# hsArduino.net
KiCad netlist of a schematic drawn in EAGLE
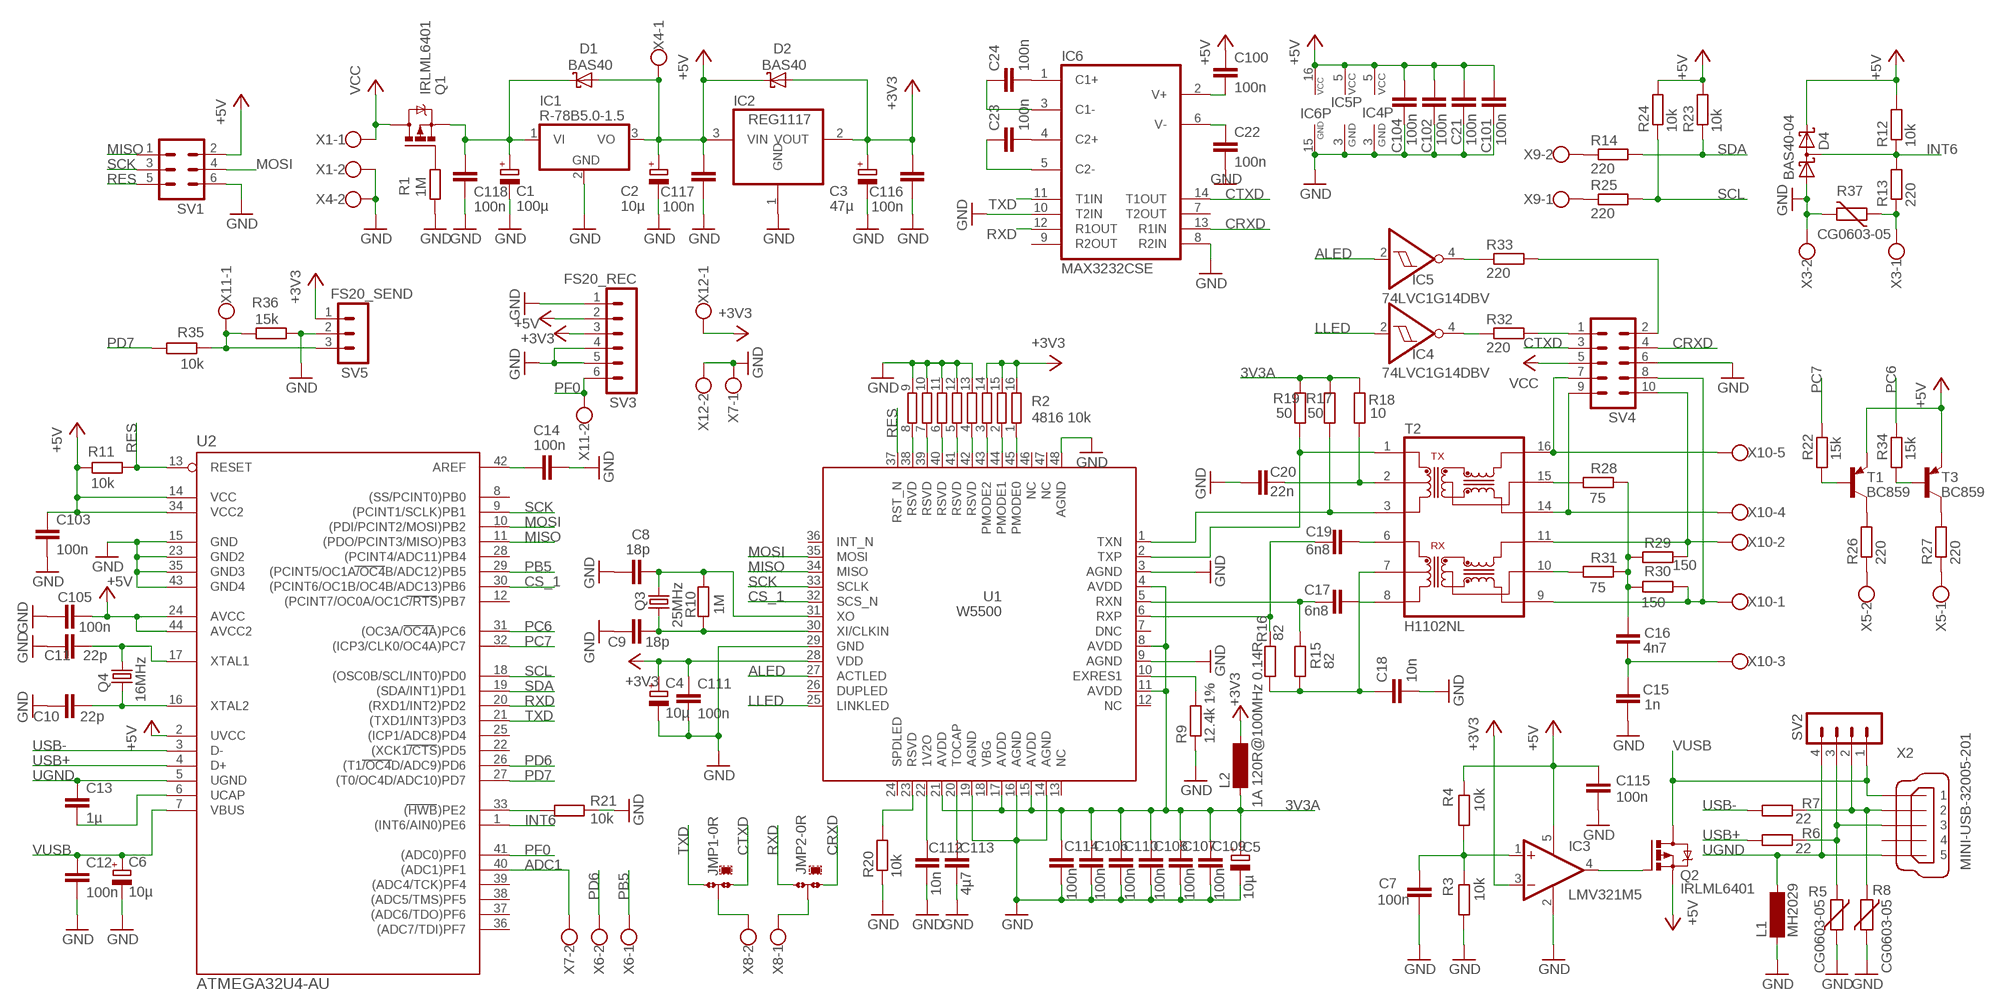
[diagram p0: schematic, sheet 1]

(export (version "E")
  (design (tool "Eeschema 10.0.6"))
  (components
    (comp (ref "C1")
      (value "100µ")
      (footprint "eagle-import:E2,5-7")
      (libsource (lib "eagle-import") (part "CPOL-EUE2.5-7"))
    )
    (comp (ref "C2")
      (value "10µ")
      (footprint "eagle-import:E2-5")
      (libsource (lib "eagle-import") (part "CPOL-EUE2-5"))
    )
    (comp (ref "C3")
      (value "47µ")
      (footprint "eagle-import:E2-5")
      (libsource (lib "eagle-import") (part "CPOL-EUE2-5"))
    )
    (comp (ref "C4")
      (value "10µ")
      (footprint "eagle-import:E2-5")
      (libsource (lib "eagle-import") (part "CPOL-EUE2-5"))
    )
    (comp (ref "C5")
      (value "10µ")
      (footprint "eagle-import:E2-5")
      (libsource (lib "eagle-import") (part "CPOL-EUE2-5"))
    )
    (comp (ref "C6")
      (value "10µ")
      (footprint "eagle-import:E2-5")
      (libsource (lib "eagle-import") (part "CPOL-EUE2-5"))
    )
    (comp (ref "C7")
      (value "100n")
      (footprint "eagle-import:C0805K")
      (libsource (lib "eagle-import") (part "C-EUC0805K"))
    )
    (comp (ref "C8")
      (value "18p")
      (footprint "eagle-import:C0805K")
      (libsource (lib "eagle-import") (part "C-EUC0805K"))
    )
    (comp (ref "C9")
      (value "18p")
      (footprint "eagle-import:C0805K")
      (libsource (lib "eagle-import") (part "C-EUC0805K"))
    )
    (comp (ref "C10")
      (value "22p")
      (footprint "eagle-import:C0805K")
      (libsource (lib "eagle-import") (part "C-EUC0805K"))
    )
    (comp (ref "C11")
      (value "22p")
      (footprint "eagle-import:C0805K")
      (libsource (lib "eagle-import") (part "C-EUC0805K"))
    )
    (comp (ref "C12")
      (value "100n")
      (footprint "eagle-import:C0805K")
      (libsource (lib "eagle-import") (part "C-EUC0805K"))
    )
    (comp (ref "C13")
      (value "1µ")
      (footprint "eagle-import:C0805K")
      (libsource (lib "eagle-import") (part "C-EUC0805K"))
    )
    (comp (ref "C14")
      (value "100n")
      (footprint "eagle-import:C0805K")
      (libsource (lib "eagle-import") (part "C-EUC0805K"))
    )
    (comp (ref "C15")
      (value "1n")
      (footprint "eagle-import:C0805K")
      (libsource (lib "eagle-import") (part "C-EUC0805K"))
    )
    (comp (ref "C16")
      (value "4n7")
      (footprint "eagle-import:C0805K")
      (libsource (lib "eagle-import") (part "C-EUC0805K"))
    )
    (comp (ref "C17")
      (value "6n8")
      (footprint "eagle-import:C0805K")
      (libsource (lib "eagle-import") (part "C-EUC0805K"))
    )
    (comp (ref "C18")
      (value "10n")
      (footprint "eagle-import:C0805K")
      (libsource (lib "eagle-import") (part "C-EUC0805K"))
    )
    (comp (ref "C19")
      (value "6n8")
      (footprint "eagle-import:C0805K")
      (libsource (lib "eagle-import") (part "C-EUC0805K"))
    )
    (comp (ref "C20")
      (value "22n")
      (footprint "eagle-import:C0805K")
      (libsource (lib "eagle-import") (part "C-EUC0805K"))
    )
    (comp (ref "C21")
      (value "100n")
      (footprint "eagle-import:C0805K")
      (libsource (lib "eagle-import") (part "C-EUC0805K"))
    )
    (comp (ref "C22")
      (value "100n")
      (footprint "eagle-import:C0805K")
      (libsource (lib "eagle-import") (part "C-EUC0805K"))
    )
    (comp (ref "C23")
      (value "100n")
      (footprint "eagle-import:C0805K")
      (libsource (lib "eagle-import") (part "C-EUC0805K"))
    )
    (comp (ref "C24")
      (value "100n")
      (footprint "eagle-import:C0805K")
      (libsource (lib "eagle-import") (part "C-EUC0805K"))
    )
    (comp (ref "C100")
      (value "100n")
      (footprint "eagle-import:C0805K")
      (libsource (lib "eagle-import") (part "C-EUC0805K"))
    )
    (comp (ref "C101")
      (value "100n")
      (footprint "eagle-import:C0805K")
      (libsource (lib "eagle-import") (part "C-EUC0805K"))
    )
    (comp (ref "C102")
      (value "100n")
      (footprint "eagle-import:C0805K")
      (libsource (lib "eagle-import") (part "C-EUC0805K"))
    )
    (comp (ref "C103")
      (value "100n")
      (footprint "eagle-import:C0805K")
      (libsource (lib "eagle-import") (part "C-EUC0805K"))
    )
    (comp (ref "C104")
      (value "100n")
      (footprint "eagle-import:C0805K")
      (libsource (lib "eagle-import") (part "C-EUC0805K"))
    )
    (comp (ref "C105")
      (value "100n")
      (footprint "eagle-import:C0805K")
      (libsource (lib "eagle-import") (part "C-EUC0805K"))
    )
    (comp (ref "C106")
      (value "100n")
      (footprint "eagle-import:C0805K")
      (libsource (lib "eagle-import") (part "C-EUC0805K"))
    )
    (comp (ref "C107")
      (value "100n")
      (footprint "eagle-import:C0805K")
      (libsource (lib "eagle-import") (part "C-EUC0805K"))
    )
    (comp (ref "C108")
      (value "100n")
      (footprint "eagle-import:C0805K")
      (libsource (lib "eagle-import") (part "C-EUC0805K"))
    )
    (comp (ref "C109")
      (value "100n")
      (footprint "eagle-import:C0805K")
      (libsource (lib "eagle-import") (part "C-EUC0805K"))
    )
    (comp (ref "C110")
      (value "100n")
      (footprint "eagle-import:C0805K")
      (libsource (lib "eagle-import") (part "C-EUC0805K"))
    )
    (comp (ref "C111")
      (value "100n")
      (footprint "eagle-import:C0805K")
      (libsource (lib "eagle-import") (part "C-EUC0805K"))
    )
    (comp (ref "C112")
      (value "10n")
      (footprint "eagle-import:C0805K")
      (libsource (lib "eagle-import") (part "C-EUC0805K"))
    )
    (comp (ref "C113")
      (value "4µ7")
      (footprint "eagle-import:C0805K")
      (libsource (lib "eagle-import") (part "C-EUC0805K"))
    )
    (comp (ref "C114")
      (value "100n")
      (footprint "eagle-import:C0805K")
      (libsource (lib "eagle-import") (part "C-EUC0805K"))
    )
    (comp (ref "C115")
      (value "100n")
      (footprint "eagle-import:C0805K")
      (libsource (lib "eagle-import") (part "C-EUC0805K"))
    )
    (comp (ref "C116")
      (value "100n")
      (footprint "eagle-import:C0805K")
      (libsource (lib "eagle-import") (part "C-EUC0805K"))
    )
    (comp (ref "C117")
      (value "100n")
      (footprint "eagle-import:C0805K")
      (libsource (lib "eagle-import") (part "C-EUC0805K"))
    )
    (comp (ref "C118")
      (value "100n")
      (footprint "eagle-import:C0805K")
      (libsource (lib "eagle-import") (part "C-EUC0805K"))
    )
    (comp (ref "D1")
      (value "BAS40")
      (footprint "eagle-import:SOT23")
      (libsource (lib "eagle-import") (part "BAS40"))
    )
    (comp (ref "D2")
      (value "BAS40")
      (footprint "eagle-import:SOT23")
      (libsource (lib "eagle-import") (part "BAS40"))
    )
    (comp (ref "D4")
      (value "BAS40-04")
      (footprint "eagle-import:SOT23")
      (libsource (lib "eagle-import") (part "BAS40-04"))
    )
    (comp (ref "IC1")
      (value "R-78B5.0-1.5")
      (footprint "eagle-import:TO220V")
      (libsource (lib "eagle-import") (part "78TV05"))
    )
    (comp (ref "IC2")
      (value "REG1117")
      (footprint "eagle-import:SOT223")
      (libsource (lib "eagle-import") (part "REG1117"))
    )
    (comp (ref "IC3")
      (value "LMV321M5")
      (footprint "eagle-import:SOT23-5")
      (libsource (lib "eagle-import") (part "LMV321?M5"))
    )
    (comp (ref "IC4")
      (value "74LVC1G14DBV")
      (footprint "eagle-import:SOT23-5")
      (libsource (lib "eagle-import") (part "741G14DBVLVC"))
    )
    (comp (ref "IC5")
      (value "74LVC1G14DBV")
      (footprint "eagle-import:SOT23-5")
      (libsource (lib "eagle-import") (part "741G14DBVLVC"))
    )
    (comp (ref "IC6")
      (value "MAX3232CSE")
      (footprint "eagle-import:SO16")
      (libsource (lib "eagle-import") (part "MAX3232SEC"))
    )
    (comp (ref "JMP1")
      (value "0R-JUMPA")
      (footprint "eagle-import:A0R-JMP")
      (libsource (lib "eagle-import") (part "0R-JUMPA"))
    )
    (comp (ref "JMP2")
      (value "0R-JUMPA")
      (footprint "eagle-import:A0R-JMP")
      (libsource (lib "eagle-import") (part "0R-JUMPA"))
    )
    (comp (ref "L1")
      (value "MH2029")
      (footprint "eagle-import:SM-1206")
      (libsource (lib "eagle-import") (part "SM-1206"))
    )
    (comp (ref "L2")
      (value "1A 120R@100MHz 0.14R")
      (footprint "eagle-import:SM-1206")
      (libsource (lib "eagle-import") (part "SM-1206"))
    )
    (comp (ref "Q1")
      (value "IRLML6401")
      (footprint "eagle-import:MICRO3")
      (libsource (lib "eagle-import") (part "IRLML5203"))
    )
    (comp (ref "Q2")
      (value "IRLML6401")
      (footprint "eagle-import:MICRO3")
      (libsource (lib "eagle-import") (part "IRLML5203"))
    )
    (comp (ref "Q3")
      (value "25MHz")
      (footprint "eagle-import:HC49_S")
      (libsource (lib "eagle-import") (part "CRYSTALHC49S"))
    )
    (comp (ref "Q4")
      (value "16MHz")
      (footprint "eagle-import:HC49_S")
      (libsource (lib "eagle-import") (part "CRYSTALHC49S"))
    )
    (comp (ref "R1")
      (value "1M")
      (footprint "eagle-import:R0805")
      (libsource (lib "eagle-import") (part "R-EU_R0805"))
    )
    (comp (ref "R2")
      (value "4816 10k")
      (footprint "eagle-import:4816P")
      (fields (field (name "MF") "BOURNS, INC.") (field (name "MPN") "4816P-T01-684LF"))
      (libsource (lib "eagle-import") (part "4816P-T01"))
    )
    (comp (ref "R3")
      (value "10k")
      (footprint "eagle-import:R0805")
      (libsource (lib "eagle-import") (part "R-EU_R0805"))
    )
    (comp (ref "R4")
      (value "10k")
      (footprint "eagle-import:R0805")
      (libsource (lib "eagle-import") (part "R-EU_R0805"))
    )
    (comp (ref "R5")
      (value "CG0603-05")
      (footprint "eagle-import:CT_CN0603")
      (libsource (lib "eagle-import") (part "VARISTORCN0603"))
    )
    (comp (ref "R6")
      (value "22")
      (footprint "eagle-import:R0805")
      (libsource (lib "eagle-import") (part "R-EU_R0805"))
    )
    (comp (ref "R7")
      (value "22")
      (footprint "eagle-import:R0805")
      (libsource (lib "eagle-import") (part "R-EU_R0805"))
    )
    (comp (ref "R8")
      (value "CG0603-05")
      (footprint "eagle-import:CT_CN0603")
      (libsource (lib "eagle-import") (part "VARISTORCN0603"))
    )
    (comp (ref "R9")
      (value "12.4k 1%")
      (footprint "eagle-import:R0805")
      (libsource (lib "eagle-import") (part "R-EU_R0805"))
    )
    (comp (ref "R10")
      (value "1M")
      (footprint "eagle-import:R0805")
      (libsource (lib "eagle-import") (part "R-EU_R0805"))
    )
    (comp (ref "R11")
      (value "10k")
      (footprint "eagle-import:R0805")
      (libsource (lib "eagle-import") (part "R-EU_R0805"))
    )
    (comp (ref "R12")
      (value "10k")
      (footprint "eagle-import:R0805")
      (libsource (lib "eagle-import") (part "R-EU_R0805"))
    )
    (comp (ref "R13")
      (value "220")
      (footprint "eagle-import:R0805")
      (libsource (lib "eagle-import") (part "R-EU_R0805"))
    )
    (comp (ref "R14")
      (value "220")
      (footprint "eagle-import:R0805")
      (libsource (lib "eagle-import") (part "R-EU_R0805"))
    )
    (comp (ref "R15")
      (value "82")
      (footprint "eagle-import:R0805")
      (libsource (lib "eagle-import") (part "R-EU_R0805"))
    )
    (comp (ref "R16")
      (value "82")
      (footprint "eagle-import:R0805")
      (libsource (lib "eagle-import") (part "R-EU_R0805"))
    )
    (comp (ref "R17")
      (value "50")
      (footprint "eagle-import:R0805")
      (libsource (lib "eagle-import") (part "R-EU_R0805"))
    )
    (comp (ref "R18")
      (value "10")
      (footprint "eagle-import:R0805")
      (libsource (lib "eagle-import") (part "R-EU_R0805"))
    )
    (comp (ref "R19")
      (value "50")
      (footprint "eagle-import:R0805")
      (libsource (lib "eagle-import") (part "R-EU_R0805"))
    )
    (comp (ref "R20")
      (value "10k")
      (footprint "eagle-import:R0805")
      (libsource (lib "eagle-import") (part "R-EU_R0805"))
    )
    (comp (ref "R21")
      (value "10k")
      (footprint "eagle-import:R0805")
      (libsource (lib "eagle-import") (part "R-EU_R0805"))
    )
    (comp (ref "R22")
      (value "15k")
      (footprint "eagle-import:R0805")
      (libsource (lib "eagle-import") (part "R-EU_R0805"))
    )
    (comp (ref "R23")
      (value "10k")
      (footprint "eagle-import:R0805")
      (libsource (lib "eagle-import") (part "R-EU_R0805"))
    )
    (comp (ref "R24")
      (value "10k")
      (footprint "eagle-import:R0805")
      (libsource (lib "eagle-import") (part "R-EU_R0805"))
    )
    (comp (ref "R25")
      (value "220")
      (footprint "eagle-import:R0805")
      (libsource (lib "eagle-import") (part "R-EU_R0805"))
    )
    (comp (ref "R26")
      (value "220")
      (footprint "eagle-import:R0805")
      (libsource (lib "eagle-import") (part "R-EU_R0805"))
    )
    (comp (ref "R27")
      (value "220")
      (footprint "eagle-import:R0805")
      (libsource (lib "eagle-import") (part "R-EU_R0805"))
    )
    (comp (ref "R28")
      (value "75")
      (footprint "eagle-import:R0805")
      (libsource (lib "eagle-import") (part "R-EU_R0805"))
    )
    (comp (ref "R29")
      (value "150")
      (footprint "eagle-import:R0805")
      (libsource (lib "eagle-import") (part "R-EU_R0805"))
    )
    (comp (ref "R30")
      (value "150")
      (footprint "eagle-import:R0805")
      (libsource (lib "eagle-import") (part "R-EU_R0805"))
    )
    (comp (ref "R31")
      (value "75")
      (footprint "eagle-import:R0805")
      (libsource (lib "eagle-import") (part "R-EU_R0805"))
    )
    (comp (ref "R32")
      (value "220")
      (footprint "eagle-import:R0805")
      (libsource (lib "eagle-import") (part "R-EU_R0805"))
    )
    (comp (ref "R33")
      (value "220")
      (footprint "eagle-import:R0805")
      (libsource (lib "eagle-import") (part "R-EU_R0805"))
    )
    (comp (ref "R34")
      (value "15k")
      (footprint "eagle-import:R0805")
      (libsource (lib "eagle-import") (part "R-EU_R0805"))
    )
    (comp (ref "R35")
      (value "10k")
      (footprint "eagle-import:R0805")
      (libsource (lib "eagle-import") (part "R-EU_R0805"))
    )
    (comp (ref "R36")
      (value "15k")
      (footprint "eagle-import:R0805")
      (libsource (lib "eagle-import") (part "R-EU_R0805"))
    )
    (comp (ref "R37")
      (value "CG0603-05")
      (footprint "eagle-import:CT_CN0603")
      (libsource (lib "eagle-import") (part "VARISTORCN0603"))
    )
    (comp (ref "SV1")
      (value "ML6")
      (footprint "eagle-import:ML6")
      (libsource (lib "eagle-import") (part "ML6"))
    )
    (comp (ref "SV2")
      (value "MA04-1")
      (footprint "eagle-import:MA04-1")
      (libsource (lib "eagle-import") (part "MA04-1"))
    )
    (comp (ref "SV3")
      (value "FS20_REC")
      (footprint "eagle-import:MA06-1")
      (libsource (lib "eagle-import") (part "MA06-1"))
    )
    (comp (ref "SV4")
      (value "ML10")
      (footprint "eagle-import:ML10")
      (libsource (lib "eagle-import") (part "ML10"))
    )
    (comp (ref "SV5")
      (value "FS20_SEND")
      (footprint "eagle-import:MA03-1")
      (libsource (lib "eagle-import") (part "MA03-1"))
    )
    (comp (ref "T1")
      (value "BC859")
      (footprint "eagle-import:SOT23-BEC")
      (libsource (lib "eagle-import") (part "-PNP-SOT23-BECBC857A"))
    )
    (comp (ref "T2")
      (value "H1102NL")
      (footprint "eagle-import:HXXXX")
      (libsource (lib "eagle-import") (part "HX1188"))
    )
    (comp (ref "T3")
      (value "BC859")
      (footprint "eagle-import:SOT23-BEC")
      (libsource (lib "eagle-import") (part "-PNP-SOT23-BECBC857A"))
    )
    (comp (ref "U1")
      (value "W5500")
      (footprint "eagle-import:W5500")
      (libsource (lib "eagle-import") (part "W5500"))
    )
    (comp (ref "U2")
      (value "ATMEGA32U4-AU")
      (footprint "eagle-import:TQFP44")
      (libsource (lib "eagle-import") (part "ATMEGA32U4-AU"))
    )
    (comp (ref "X1")
      (value "W237-02P")
      (footprint "eagle-import:W237-132")
      (libsource (lib "eagle-import") (part "W237-02P"))
    )
    (comp (ref "X2")
      (value "MINI-USB-32005-201")
      (footprint "eagle-import:32005-201")
      (libsource (lib "eagle-import") (part "MINI-USB-32005-201"))
    )
    (comp (ref "X3")
      (value "W237-02P")
      (footprint "eagle-import:W237-132")
      (libsource (lib "eagle-import") (part "W237-02P"))
    )
    (comp (ref "X4")
      (value "W237-02P")
      (footprint "eagle-import:W237-132")
      (libsource (lib "eagle-import") (part "W237-02P"))
    )
    (comp (ref "X5")
      (value "W237-02P")
      (footprint "eagle-import:W237-132")
      (libsource (lib "eagle-import") (part "W237-02P"))
    )
    (comp (ref "X6")
      (value "W237-02P")
      (footprint "eagle-import:W237-132")
      (libsource (lib "eagle-import") (part "W237-02P"))
    )
    (comp (ref "X7")
      (value "W237-02P")
      (footprint "eagle-import:W237-132")
      (libsource (lib "eagle-import") (part "W237-02P"))
    )
    (comp (ref "X8")
      (value "W237-02P")
      (footprint "eagle-import:W237-132")
      (libsource (lib "eagle-import") (part "W237-02P"))
    )
    (comp (ref "X9")
      (value "W237-02P")
      (footprint "eagle-import:W237-132")
      (libsource (lib "eagle-import") (part "W237-02P"))
    )
    (comp (ref "X10")
      (value "W237-05P")
      (footprint "eagle-import:W237-5P")
      (libsource (lib "eagle-import") (part "W237-05P"))
    )
    (comp (ref "X11")
      (value "W237-02P")
      (footprint "eagle-import:W237-132")
      (libsource (lib "eagle-import") (part "W237-02P"))
    )
    (comp (ref "X12")
      (value "W237-02P")
      (footprint "eagle-import:W237-132")
      (libsource (lib "eagle-import") (part "W237-02P"))
    )
  )
  (nets
    (net (code "1") (name "+3V3") (class "Default")
      (node (ref "C111") (pin "1") (pinfunction "1_1") (pintype "passive"))
      (node (ref "C116") (pin "2") (pinfunction "2_2") (pintype "passive"))
      (node (ref "C3") (pin "+") (pinfunction "+_+") (pintype "passive"))
      (node (ref "C4") (pin "+") (pinfunction "+_+") (pintype "passive"))
      (node (ref "D2") (pin "1") (pinfunction "A_1") (pintype "passive"))
      (node (ref "IC2") (pin "2") (pinfunction "VOUT_2") (pintype "output"))
      (node (ref "IC3") (pin "3") (pinfunction "-IN_3") (pintype "input"))
      (node (ref "L2") (pin "2") (pinfunction "2_2") (pintype "passive"))
      (node (ref "R2") (pin "14") (pinfunction "14_14") (pintype "passive"))
      (node (ref "R2") (pin "15") (pinfunction "15_15") (pintype "passive"))
      (node (ref "R2") (pin "16") (pinfunction "16_16") (pintype "passive"))
      (node (ref "SV3") (pin "3") (pinfunction "3_3") (pintype "passive"))
      (node (ref "SV5") (pin "1") (pinfunction "1_1") (pintype "passive"))
      (node (ref "U1") (pin "28") (pinfunction "VDD_28") (pintype "passive"))
      (node (ref "X12") (pin "1") (pinfunction "KL_1") (pintype "passive"))
    )
    (net (code "2") (name "+5V") (class "Default")
      (node (ref "C100") (pin "1") (pinfunction "1_1") (pintype "passive"))
      (node (ref "C101") (pin "1") (pinfunction "1_1") (pintype "passive"))
      (node (ref "C102") (pin "2") (pinfunction "2_2") (pintype "passive"))
      (node (ref "C103") (pin "1") (pinfunction "1_1") (pintype "passive"))
      (node (ref "C104") (pin "2") (pinfunction "2_2") (pintype "passive"))
      (node (ref "C105") (pin "1") (pinfunction "1_1") (pintype "passive"))
      (node (ref "C115") (pin "2") (pinfunction "2_2") (pintype "passive"))
      (node (ref "C117") (pin "2") (pinfunction "2_2") (pintype "passive"))
      (node (ref "C2") (pin "+") (pinfunction "+_+") (pintype "passive"))
      (node (ref "C21") (pin "1") (pinfunction "1_1") (pintype "passive"))
      (node (ref "D1") (pin "1") (pinfunction "A_1") (pintype "passive"))
      (node (ref "D2") (pin "3") (pinfunction "C_3") (pintype "passive"))
      (node (ref "D4") (pin "2") (pinfunction "C2_2") (pintype "passive"))
      (node (ref "IC1") (pin "3") (pinfunction "VO_3") (pintype "passive"))
      (node (ref "IC2") (pin "3") (pinfunction "VIN_3") (pintype "input"))
      (node (ref "IC3") (pin "5") (pinfunction "V+_5") (pintype "power_in"))
      (node (ref "IC4") (pin "5") (pinfunction "VCC_5") (pintype "power_in"))
      (node (ref "IC5") (pin "5") (pinfunction "VCC_5") (pintype "power_in"))
      (node (ref "IC6") (pin "16") (pinfunction "VCC_16") (pintype "power_in"))
      (node (ref "Q2") (pin "2") (pinfunction "S_2") (pintype "passive"))
      (node (ref "R11") (pin "2") (pinfunction "2_2") (pintype "passive"))
      (node (ref "R12") (pin "2") (pinfunction "2_2") (pintype "passive"))
      (node (ref "R23") (pin "2") (pinfunction "2_2") (pintype "passive"))
      (node (ref "R24") (pin "2") (pinfunction "2_2") (pintype "passive"))
      (node (ref "R4") (pin "1") (pinfunction "1_1") (pintype "passive"))
      (node (ref "SV1") (pin "2") (pinfunction "2_2") (pintype "passive"))
      (node (ref "SV3") (pin "2") (pinfunction "2_2") (pintype "passive"))
      (node (ref "T1") (pin "E") (pinfunction "E_E") (pintype "passive"))
      (node (ref "T3") (pin "E") (pinfunction "E_E") (pintype "passive"))
      (node (ref "U2") (pin "14") (pinfunction "VCC_14") (pintype "bidirectional"))
      (node (ref "U2") (pin "2") (pinfunction "UVCC_2") (pintype "bidirectional"))
      (node (ref "U2") (pin "24") (pinfunction "AVCC_24") (pintype "bidirectional"))
      (node (ref "U2") (pin "34") (pinfunction "VCC2_34") (pintype "bidirectional"))
      (node (ref "U2") (pin "44") (pinfunction "AVCC2_44") (pintype "bidirectional"))
      (node (ref "X4") (pin "1") (pinfunction "KL_1") (pintype "passive"))
    )
    (net (code "3") (name "/3V3A") (class "Default")
      (node (ref "C106") (pin "1") (pinfunction "1_1") (pintype "passive"))
      (node (ref "C107") (pin "1") (pinfunction "1_1") (pintype "passive"))
      (node (ref "C108") (pin "1") (pinfunction "1_1") (pintype "passive"))
      (node (ref "C109") (pin "1") (pinfunction "1_1") (pintype "passive"))
      (node (ref "C110") (pin "1") (pinfunction "1_1") (pintype "passive"))
      (node (ref "C114") (pin "1") (pinfunction "1_1") (pintype "passive"))
      (node (ref "C5") (pin "+") (pinfunction "+_+") (pintype "passive"))
      (node (ref "L2") (pin "1") (pinfunction "1_1") (pintype "passive"))
      (node (ref "R17") (pin "2") (pinfunction "2_2") (pintype "passive"))
      (node (ref "R18") (pin "2") (pinfunction "2_2") (pintype "passive"))
      (node (ref "R19") (pin "2") (pinfunction "2_2") (pintype "passive"))
      (node (ref "U1") (pin "11") (pinfunction "AVDD_11") (pintype "passive"))
      (node (ref "U1") (pin "15") (pinfunction "AVDD_15") (pintype "passive"))
      (node (ref "U1") (pin "17") (pinfunction "AVDD_17") (pintype "passive"))
      (node (ref "U1") (pin "21") (pinfunction "AVDD_21") (pintype "passive"))
      (node (ref "U1") (pin "4") (pinfunction "AVDD_4") (pintype "passive"))
      (node (ref "U1") (pin "8") (pinfunction "AVDD_8") (pintype "passive"))
    )
    (net (code "4") (name "/ADC1") (class "Default")
      (node (ref "U2") (pin "40") (pinfunction "(ADC1)PF1_40") (pintype "bidirectional"))
      (node (ref "X7") (pin "2") (pinfunction "KL_2") (pintype "passive"))
    )
    (net (code "5") (name "/ALED") (class "Default")
      (node (ref "IC5") (pin "2") (pinfunction "I_2") (pintype "input"))
      (node (ref "U1") (pin "27") (pinfunction "ACTLED_27") (pintype "passive"))
    )
    (net (code "6") (name "/CRXD") (class "Default")
      (node (ref "IC6") (pin "13") (pinfunction "R1IN_13") (pintype "input"))
      (node (ref "JMP2") (pin "1") (pinfunction "1_1") (pintype "passive"))
      (node (ref "SV4") (pin "4") (pinfunction "4_4") (pintype "passive"))
    )
    (net (code "7") (name "/CS_1") (class "Default")
      (node (ref "U1") (pin "32") (pinfunction "SCS_N_32") (pintype "passive"))
      (node (ref "U2") (pin "30") (pinfunction "(PCINT6/OC1B/OC4B/ADC13)PB6_30") (pintype "bidirectional"))
    )
    (net (code "8") (name "/CTXD") (class "Default")
      (node (ref "IC6") (pin "14") (pinfunction "T1OUT_14") (pintype "output"))
      (node (ref "JMP1") (pin "1") (pinfunction "1_1") (pintype "passive"))
      (node (ref "SV4") (pin "3") (pinfunction "3_3") (pintype "passive"))
    )
    (net (code "9") (name "/INT6") (class "Default")
      (node (ref "D4") (pin "3") (pinfunction "C1A2_3") (pintype "passive"))
      (node (ref "R12") (pin "1") (pinfunction "1_1") (pintype "passive"))
      (node (ref "R13") (pin "2") (pinfunction "2_2") (pintype "passive"))
      (node (ref "U2") (pin "1") (pinfunction "(INT6/AIN0)PE6_1") (pintype "bidirectional"))
    )
    (net (code "10") (name "/LLED") (class "Default")
      (node (ref "IC4") (pin "2") (pinfunction "I_2") (pintype "input"))
      (node (ref "U1") (pin "25") (pinfunction "LINKLED_25") (pintype "passive"))
    )
    (net (code "11") (name "/MISO") (class "Default")
      (node (ref "SV1") (pin "1") (pinfunction "1_1") (pintype "passive"))
      (node (ref "U1") (pin "34") (pinfunction "MISO_34") (pintype "passive"))
      (node (ref "U2") (pin "11") (pinfunction "(PDO/PCINT3/MISO)PB3_11") (pintype "bidirectional"))
    )
    (net (code "12") (name "/MOSI") (class "Default")
      (node (ref "SV1") (pin "4") (pinfunction "4_4") (pintype "passive"))
      (node (ref "U1") (pin "35") (pinfunction "MOSI_35") (pintype "passive"))
      (node (ref "U2") (pin "10") (pinfunction "(PDI/PCINT2/MOSI)PB2_10") (pintype "bidirectional"))
    )
    (net (code "13") (name "/PB5") (class "Default")
      (node (ref "U2") (pin "29") (pinfunction "(PCINT5/OC1A/OC4B/ADC12)PB5_29") (pintype "bidirectional"))
      (node (ref "X6") (pin "1") (pinfunction "KL_1") (pintype "passive"))
    )
    (net (code "14") (name "/PC6") (class "Default")
      (node (ref "R34") (pin "2") (pinfunction "2_2") (pintype "passive"))
      (node (ref "U2") (pin "31") (pinfunction "(OC3A/OC4A)PC6_31") (pintype "bidirectional"))
    )
    (net (code "15") (name "/PC7") (class "Default")
      (node (ref "R22") (pin "2") (pinfunction "2_2") (pintype "passive"))
      (node (ref "U2") (pin "32") (pinfunction "(ICP3/CLK0/OC4A)PC7_32") (pintype "bidirectional"))
    )
    (net (code "16") (name "/PD6") (class "Default")
      (node (ref "U2") (pin "26") (pinfunction "(T1/OC4D/ADC9)PD6_26") (pintype "bidirectional"))
      (node (ref "X6") (pin "2") (pinfunction "KL_2") (pintype "passive"))
    )
    (net (code "17") (name "/PD7") (class "Default")
      (node (ref "R35") (pin "2") (pinfunction "2_2") (pintype "passive"))
      (node (ref "U2") (pin "27") (pinfunction "(T0/OC4D/ADC10)PD7_27") (pintype "bidirectional"))
    )
    (net (code "18") (name "/PF0") (class "Default")
      (node (ref "SV3") (pin "6") (pinfunction "6_6") (pintype "passive"))
      (node (ref "U2") (pin "41") (pinfunction "(ADC0)PF0_41") (pintype "bidirectional"))
      (node (ref "X11") (pin "2") (pinfunction "KL_2") (pintype "passive"))
    )
    (net (code "19") (name "/RES") (class "Default")
      (node (ref "R11") (pin "1") (pinfunction "1_1") (pintype "passive"))
      (node (ref "SV1") (pin "5") (pinfunction "5_5") (pintype "passive"))
      (node (ref "U1") (pin "37") (pinfunction "RST_N_37") (pintype "passive"))
      (node (ref "U2") (pin "13") (pinfunction "RESET_13") (pintype "bidirectional"))
    )
    (net (code "20") (name "/RXD") (class "Default")
      (node (ref "IC6") (pin "12") (pinfunction "R1OUT_12") (pintype "output"))
      (node (ref "JMP2") (pin "3") (pinfunction "3_3") (pintype "passive"))
      (node (ref "U2") (pin "20") (pinfunction "(RXD1/INT2)PD2_20") (pintype "bidirectional"))
    )
    (net (code "21") (name "/SCK") (class "Default")
      (node (ref "SV1") (pin "3") (pinfunction "3_3") (pintype "passive"))
      (node (ref "U1") (pin "33") (pinfunction "SCLK_33") (pintype "passive"))
      (node (ref "U2") (pin "9") (pinfunction "(PCINT1/SCLK)PB1_9") (pintype "bidirectional"))
    )
    (net (code "22") (name "/SCL") (class "Default")
      (node (ref "R24") (pin "1") (pinfunction "1_1") (pintype "passive"))
      (node (ref "R25") (pin "2") (pinfunction "2_2") (pintype "passive"))
      (node (ref "U2") (pin "18") (pinfunction "(OSC0B/SCL/INT0)PD0_18") (pintype "bidirectional"))
    )
    (net (code "23") (name "/SDA") (class "Default")
      (node (ref "R14") (pin "2") (pinfunction "2_2") (pintype "passive"))
      (node (ref "R23") (pin "1") (pinfunction "1_1") (pintype "passive"))
      (node (ref "U2") (pin "19") (pinfunction "(SDA/INT1)PD1_19") (pintype "bidirectional"))
    )
    (net (code "24") (name "/TXD") (class "Default")
      (node (ref "IC6") (pin "11") (pinfunction "T1IN_11") (pintype "input"))
      (node (ref "JMP1") (pin "3") (pinfunction "3_3") (pintype "passive"))
      (node (ref "U2") (pin "21") (pinfunction "(TXD1/INT3)PD3_21") (pintype "bidirectional"))
    )
    (net (code "25") (name "/UGND") (class "Default")
      (node (ref "C13") (pin "1") (pinfunction "1_1") (pintype "passive"))
      (node (ref "L1") (pin "2") (pinfunction "2_2") (pintype "passive"))
      (node (ref "SV2") (pin "4") (pinfunction "4_4") (pintype "passive"))
      (node (ref "U2") (pin "5") (pinfunction "UGND_5") (pintype "bidirectional"))
      (node (ref "X2") (pin "5") (pinfunction "5_5") (pintype "passive"))
    )
    (net (code "26") (name "/USB+") (class "Default")
      (node (ref "R6") (pin "2") (pinfunction "2_2") (pintype "passive"))
      (node (ref "U2") (pin "4") (pinfunction "D+_4") (pintype "bidirectional"))
    )
    (net (code "27") (name "/USB-") (class "Default")
      (node (ref "R7") (pin "2") (pinfunction "2_2") (pintype "passive"))
      (node (ref "U2") (pin "3") (pinfunction "D-_3") (pintype "bidirectional"))
    )
    (net (code "28") (name "/VUSB") (class "Default")
      (node (ref "C12") (pin "1") (pinfunction "1_1") (pintype "passive"))
      (node (ref "C6") (pin "+") (pinfunction "+_+") (pintype "passive"))
      (node (ref "Q2") (pin "3") (pinfunction "D_3") (pintype "passive"))
      (node (ref "SV2") (pin "1") (pinfunction "1_1") (pintype "passive"))
      (node (ref "U2") (pin "7") (pinfunction "VBUS_7") (pintype "bidirectional"))
      (node (ref "X2") (pin "1") (pinfunction "1_1") (pintype "passive"))
    )
    (net (code "29") (name "GND") (class "Default")
      (node (ref "C1") (pin "-") (pinfunction "-_-") (pintype "passive"))
      (node (ref "C10") (pin "2") (pinfunction "2_2") (pintype "passive"))
      (node (ref "C101") (pin "2") (pinfunction "2_2") (pintype "passive"))
      (node (ref "C102") (pin "1") (pinfunction "1_1") (pintype "passive"))
      (node (ref "C103") (pin "2") (pinfunction "2_2") (pintype "passive"))
      (node (ref "C104") (pin "1") (pinfunction "1_1") (pintype "passive"))
      (node (ref "C105") (pin "2") (pinfunction "2_2") (pintype "passive"))
      (node (ref "C106") (pin "2") (pinfunction "2_2") (pintype "passive"))
      (node (ref "C107") (pin "2") (pinfunction "2_2") (pintype "passive"))
      (node (ref "C108") (pin "2") (pinfunction "2_2") (pintype "passive"))
      (node (ref "C109") (pin "2") (pinfunction "2_2") (pintype "passive"))
      (node (ref "C11") (pin "1") (pinfunction "1_1") (pintype "passive"))
      (node (ref "C110") (pin "2") (pinfunction "2_2") (pintype "passive"))
      (node (ref "C111") (pin "2") (pinfunction "2_2") (pintype "passive"))
      (node (ref "C112") (pin "2") (pinfunction "2_2") (pintype "passive"))
      (node (ref "C113") (pin "2") (pinfunction "2_2") (pintype "passive"))
      (node (ref "C114") (pin "2") (pinfunction "2_2") (pintype "passive"))
      (node (ref "C115") (pin "1") (pinfunction "1_1") (pintype "passive"))
      (node (ref "C116") (pin "1") (pinfunction "1_1") (pintype "passive"))
      (node (ref "C117") (pin "1") (pinfunction "1_1") (pintype "passive"))
      (node (ref "C118") (pin "2") (pinfunction "2_2") (pintype "passive"))
      (node (ref "C12") (pin "2") (pinfunction "2_2") (pintype "passive"))
      (node (ref "C14") (pin "2") (pinfunction "2_2") (pintype "passive"))
      (node (ref "C15") (pin "1") (pinfunction "1_1") (pintype "passive"))
      (node (ref "C18") (pin "2") (pinfunction "2_2") (pintype "passive"))
      (node (ref "C2") (pin "-") (pinfunction "-_-") (pintype "passive"))
      (node (ref "C20") (pin "1") (pinfunction "1_1") (pintype "passive"))
      (node (ref "C21") (pin "2") (pinfunction "2_2") (pintype "passive"))
      (node (ref "C22") (pin "2") (pinfunction "2_2") (pintype "passive"))
      (node (ref "C3") (pin "-") (pinfunction "-_-") (pintype "passive"))
      (node (ref "C4") (pin "-") (pinfunction "-_-") (pintype "passive"))
      (node (ref "C5") (pin "-") (pinfunction "-_-") (pintype "passive"))
      (node (ref "C6") (pin "-") (pinfunction "-_-") (pintype "passive"))
      (node (ref "C7") (pin "2") (pinfunction "2_2") (pintype "passive"))
      (node (ref "C8") (pin "1") (pinfunction "1_1") (pintype "passive"))
      (node (ref "C9") (pin "2") (pinfunction "2_2") (pintype "passive"))
      (node (ref "D4") (pin "1") (pinfunction "A1_1") (pintype "passive"))
      (node (ref "IC1") (pin "2") (pinfunction "GND_2") (pintype "passive"))
      (node (ref "IC2") (pin "1") (pinfunction "GND_1") (pintype "power_in"))
      (node (ref "IC3") (pin "2") (pinfunction "V-_2") (pintype "power_in"))
      (node (ref "IC4") (pin "3") (pinfunction "GND_3") (pintype "power_in"))
      (node (ref "IC5") (pin "3") (pinfunction "GND_3") (pintype "power_in"))
      (node (ref "IC6") (pin "10") (pinfunction "T2IN_10") (pintype "input"))
      (node (ref "IC6") (pin "15") (pinfunction "GND_15") (pintype "power_in"))
      (node (ref "IC6") (pin "8") (pinfunction "R2IN_8") (pintype "input"))
      (node (ref "L1") (pin "1") (pinfunction "1_1") (pintype "passive"))
      (node (ref "R1") (pin "2") (pinfunction "2_2") (pintype "passive"))
      (node (ref "R2") (pin "10") (pinfunction "10_10") (pintype "passive"))
      (node (ref "R2") (pin "11") (pinfunction "11_11") (pintype "passive"))
      (node (ref "R2") (pin "12") (pinfunction "12_12") (pintype "passive"))
      (node (ref "R2") (pin "13") (pinfunction "13_13") (pintype "passive"))
      (node (ref "R2") (pin "9") (pinfunction "9_9") (pintype "passive"))
      (node (ref "R20") (pin "1") (pinfunction "1_1") (pintype "passive"))
      (node (ref "R21") (pin "2") (pinfunction "2_2") (pintype "passive"))
      (node (ref "R3") (pin "2") (pinfunction "2_2") (pintype "passive"))
      (node (ref "R36") (pin "1") (pinfunction "1_1") (pintype "passive"))
      (node (ref "R37") (pin "2") (pinfunction "2_2") (pintype "passive"))
      (node (ref "R5") (pin "2") (pinfunction "2_2") (pintype "passive"))
      (node (ref "R8") (pin "2") (pinfunction "2_2") (pintype "passive"))
      (node (ref "R9") (pin "1") (pinfunction "1_1") (pintype "passive"))
      (node (ref "SV1") (pin "6") (pinfunction "6_6") (pintype "passive"))
      (node (ref "SV3") (pin "1") (pinfunction "1_1") (pintype "passive"))
      (node (ref "SV3") (pin "4") (pinfunction "4_4") (pintype "passive"))
      (node (ref "SV3") (pin "5") (pinfunction "5_5") (pintype "passive"))
      (node (ref "SV4") (pin "6") (pinfunction "6_6") (pintype "passive"))
      (node (ref "SV5") (pin "2") (pinfunction "2_2") (pintype "passive"))
      (node (ref "U1") (pin "14") (pinfunction "AGND_14") (pintype "passive"))
      (node (ref "U1") (pin "16") (pinfunction "AGND_16") (pintype "passive"))
      (node (ref "U1") (pin "19") (pinfunction "AGND_19") (pintype "passive"))
      (node (ref "U1") (pin "29") (pinfunction "GND_29") (pintype "passive"))
      (node (ref "U1") (pin "3") (pinfunction "AGND_3") (pintype "passive"))
      (node (ref "U1") (pin "48") (pinfunction "AGND_48") (pintype "passive"))
      (node (ref "U1") (pin "9") (pinfunction "AGND_9") (pintype "passive"))
      (node (ref "U2") (pin "15") (pinfunction "GND_15") (pintype "bidirectional"))
      (node (ref "U2") (pin "23") (pinfunction "GND2_23") (pintype "bidirectional"))
      (node (ref "U2") (pin "35") (pinfunction "GND3_35") (pintype "bidirectional"))
      (node (ref "U2") (pin "43") (pinfunction "GND4_43") (pintype "bidirectional"))
      (node (ref "X1") (pin "2") (pinfunction "KL_2") (pintype "passive"))
      (node (ref "X12") (pin "2") (pinfunction "KL_2") (pintype "passive"))
      (node (ref "X3") (pin "2") (pinfunction "KL_2") (pintype "passive"))
      (node (ref "X4") (pin "2") (pinfunction "KL_2") (pintype "passive"))
      (node (ref "X7") (pin "1") (pinfunction "KL_1") (pintype "passive"))
    )
    (net (code "30") (name "Net-(C16-Pad2)") (class "Default")
      (node (ref "C16") (pin "2") (pinfunction "2_2") (pintype "passive"))
      (node (ref "R28") (pin "1") (pinfunction "1_1") (pintype "passive"))
      (node (ref "R29") (pin "2") (pinfunction "2_2") (pintype "passive"))
      (node (ref "R30") (pin "2") (pinfunction "2_2") (pintype "passive"))
      (node (ref "R31") (pin "1") (pinfunction "1_1") (pintype "passive"))
    )
    (net (code "31") (name "Net-(C17-Pad2)") (class "Default")
      (node (ref "C17") (pin "2") (pinfunction "2_2") (pintype "passive"))
      (node (ref "T2") (pin "8") (pinfunction "8_8") (pintype "passive"))
    )
    (net (code "32") (name "Net-(C18-Pad1)") (class "Default")
      (node (ref "C18") (pin "1") (pinfunction "1_1") (pintype "passive"))
      (node (ref "R15") (pin "2") (pinfunction "2_2") (pintype "passive"))
      (node (ref "R16") (pin "2") (pinfunction "2_2") (pintype "passive"))
      (node (ref "T2") (pin "7") (pinfunction "7_7") (pintype "passive"))
    )
    (net (code "33") (name "Net-(C19-Pad2)") (class "Default")
      (node (ref "C19") (pin "2") (pinfunction "2_2") (pintype "passive"))
      (node (ref "T2") (pin "6") (pinfunction "6_6") (pintype "passive"))
    )
    (net (code "34") (name "Net-(C20-Pad2)") (class "Default")
      (node (ref "C20") (pin "2") (pinfunction "2_2") (pintype "passive"))
      (node (ref "R18") (pin "1") (pinfunction "1_1") (pintype "passive"))
      (node (ref "T2") (pin "2") (pinfunction "2_2") (pintype "passive"))
    )
    (net (code "35") (name "Net-(D1-C)") (class "Default")
      (node (ref "C1") (pin "+") (pinfunction "+_+") (pintype "passive"))
      (node (ref "C118") (pin "1") (pinfunction "1_1") (pintype "passive"))
      (node (ref "D1") (pin "3") (pinfunction "C_3") (pintype "passive"))
      (node (ref "IC1") (pin "1") (pinfunction "VI_1") (pintype "input"))
      (node (ref "Q1") (pin "2") (pinfunction "S_2") (pintype "passive"))
    )
    (net (code "36") (name "Net-(IC3-+IN)") (class "Default")
      (node (ref "C7") (pin "1") (pinfunction "1_1") (pintype "passive"))
      (node (ref "IC3") (pin "1") (pinfunction "+IN_1") (pintype "input"))
      (node (ref "R3") (pin "1") (pinfunction "1_1") (pintype "passive"))
      (node (ref "R4") (pin "2") (pinfunction "2_2") (pintype "passive"))
    )
    (net (code "37") (name "Net-(IC3-OUT)") (class "Default")
      (node (ref "IC3") (pin "4") (pinfunction "OUT_4") (pintype "output"))
      (node (ref "Q2") (pin "1") (pinfunction "G_1") (pintype "passive"))
    )
    (net (code "38") (name "Net-(IC4A-O)") (class "Default")
      (node (ref "IC4") (pin "4") (pinfunction "O_4") (pintype "output"))
      (node (ref "R32") (pin "1") (pinfunction "1_1") (pintype "passive"))
    )
    (net (code "39") (name "Net-(IC5A-O)") (class "Default")
      (node (ref "IC5") (pin "4") (pinfunction "O_4") (pintype "output"))
      (node (ref "R33") (pin "1") (pinfunction "1_1") (pintype "passive"))
    )
    (net (code "40") (name "Net-(IC6A-C1+)") (class "Default")
      (node (ref "C24") (pin "2") (pinfunction "2_2") (pintype "passive"))
      (node (ref "IC6") (pin "1") (pinfunction "C1+_1") (pintype "bidirectional"))
    )
    (net (code "41") (name "Net-(IC6A-C1-)") (class "Default")
      (node (ref "C24") (pin "1") (pinfunction "1_1") (pintype "passive"))
      (node (ref "IC6") (pin "3") (pinfunction "C1-_3") (pintype "bidirectional"))
    )
    (net (code "42") (name "Net-(IC6A-C2+)") (class "Default")
      (node (ref "C23") (pin "2") (pinfunction "2_2") (pintype "passive"))
      (node (ref "IC6") (pin "4") (pinfunction "C2+_4") (pintype "bidirectional"))
    )
    (net (code "43") (name "Net-(IC6A-C2-)") (class "Default")
      (node (ref "C23") (pin "1") (pinfunction "1_1") (pintype "passive"))
      (node (ref "IC6") (pin "5") (pinfunction "C2-_5") (pintype "bidirectional"))
    )
    (net (code "44") (name "Net-(IC6A-V+)") (class "Default")
      (node (ref "C100") (pin "2") (pinfunction "2_2") (pintype "passive"))
      (node (ref "IC6") (pin "2") (pinfunction "V+_2") (pintype "bidirectional"))
    )
    (net (code "45") (name "Net-(IC6A-V-)") (class "Default")
      (node (ref "C22") (pin "1") (pinfunction "1_1") (pintype "passive"))
      (node (ref "IC6") (pin "6") (pinfunction "V-_6") (pintype "bidirectional"))
    )
    (net (code "46") (name "Net-(Q1-G)") (class "Default")
      (node (ref "Q1") (pin "1") (pinfunction "G_1") (pintype "passive"))
      (node (ref "R1") (pin "1") (pinfunction "1_1") (pintype "passive"))
    )
    (net (code "47") (name "Net-(R2-Pad4)") (class "Default")
      (node (ref "R2") (pin "4") (pinfunction "4_4") (pintype "passive"))
      (node (ref "U1") (pin "42") (pinfunction "RSVD_42") (pintype "passive"))
    )
    (net (code "48") (name "Net-(R2-Pad5)") (class "Default")
      (node (ref "R2") (pin "5") (pinfunction "5_5") (pintype "passive"))
      (node (ref "U1") (pin "41") (pinfunction "RSVD_41") (pintype "passive"))
    )
    (net (code "49") (name "Net-(R2-Pad6)") (class "Default")
      (node (ref "R2") (pin "6") (pinfunction "6_6") (pintype "passive"))
      (node (ref "U1") (pin "40") (pinfunction "RSVD_40") (pintype "passive"))
    )
    (net (code "50") (name "Net-(R2-Pad7)") (class "Default")
      (node (ref "R2") (pin "7") (pinfunction "7_7") (pintype "passive"))
      (node (ref "U1") (pin "39") (pinfunction "RSVD_39") (pintype "passive"))
    )
    (net (code "51") (name "Net-(R2-Pad8)") (class "Default")
      (node (ref "R2") (pin "8") (pinfunction "8_8") (pintype "passive"))
      (node (ref "U1") (pin "38") (pinfunction "RSVD_38") (pintype "passive"))
    )
    (net (code "52") (name "Net-(R5-Pad1)") (class "Default")
      (node (ref "R5") (pin "1") (pinfunction "1_1") (pintype "passive"))
      (node (ref "R6") (pin "1") (pinfunction "1_1") (pintype "passive"))
      (node (ref "SV2") (pin "3") (pinfunction "3_3") (pintype "passive"))
      (node (ref "X2") (pin "3") (pinfunction "3_3") (pintype "passive"))
    )
    (net (code "53") (name "Net-(R7-Pad1)") (class "Default")
      (node (ref "R7") (pin "1") (pinfunction "1_1") (pintype "passive"))
      (node (ref "R8") (pin "1") (pinfunction "1_1") (pintype "passive"))
      (node (ref "SV2") (pin "2") (pinfunction "2_2") (pintype "passive"))
      (node (ref "X2") (pin "2") (pinfunction "2_2") (pintype "passive"))
    )
    (net (code "54") (name "Net-(R20-Pad2)") (class "Default")
      (node (ref "R20") (pin "2") (pinfunction "2_2") (pintype "passive"))
      (node (ref "U1") (pin "23") (pinfunction "RSVD_23") (pintype "passive"))
    )
    (net (code "55") (name "Net-(R22-Pad1)") (class "Default")
      (node (ref "R22") (pin "1") (pinfunction "1_1") (pintype "passive"))
      (node (ref "T1") (pin "B") (pinfunction "B_B") (pintype "passive"))
    )
    (net (code "56") (name "Net-(R26-Pad2)") (class "Default")
      (node (ref "R26") (pin "2") (pinfunction "2_2") (pintype "passive"))
      (node (ref "T1") (pin "C") (pinfunction "C_C") (pintype "passive"))
    )
    (net (code "57") (name "Net-(R27-Pad2)") (class "Default")
      (node (ref "R27") (pin "2") (pinfunction "2_2") (pintype "passive"))
      (node (ref "T3") (pin "C") (pinfunction "C_C") (pintype "passive"))
    )
    (net (code "58") (name "Net-(R28-Pad2)") (class "Default")
      (node (ref "R28") (pin "2") (pinfunction "2_2") (pintype "passive"))
      (node (ref "T2") (pin "15") (pinfunction "15_15") (pintype "passive"))
    )
    (net (code "59") (name "Net-(R31-Pad2)") (class "Default")
      (node (ref "R31") (pin "2") (pinfunction "2_2") (pintype "passive"))
      (node (ref "T2") (pin "10") (pinfunction "10_10") (pintype "passive"))
    )
    (net (code "60") (name "Net-(R32-Pad2)") (class "Default")
      (node (ref "R32") (pin "2") (pinfunction "2_2") (pintype "passive"))
      (node (ref "SV4") (pin "1") (pinfunction "1_1") (pintype "passive"))
    )
    (net (code "61") (name "Net-(R33-Pad2)") (class "Default")
      (node (ref "R33") (pin "2") (pinfunction "2_2") (pintype "passive"))
      (node (ref "SV4") (pin "2") (pinfunction "2_2") (pintype "passive"))
    )
    (net (code "62") (name "Net-(R34-Pad1)") (class "Default")
      (node (ref "R34") (pin "1") (pinfunction "1_1") (pintype "passive"))
      (node (ref "T3") (pin "B") (pinfunction "B_B") (pintype "passive"))
    )
    (net (code "63") (name "Net-(U1-1V2O)") (class "Default")
      (node (ref "C112") (pin "1") (pinfunction "1_1") (pintype "passive"))
      (node (ref "U1") (pin "22") (pinfunction "1V2O_22") (pintype "passive"))
    )
    (net (code "64") (name "Net-(U1-EXRES1)") (class "Default")
      (node (ref "R9") (pin "2") (pinfunction "2_2") (pintype "passive"))
      (node (ref "U1") (pin "10") (pinfunction "EXRES1_10") (pintype "passive"))
    )
    (net (code "65") (name "Net-(U1-PMODE0)") (class "Default")
      (node (ref "R2") (pin "1") (pinfunction "1_1") (pintype "passive"))
      (node (ref "U1") (pin "45") (pinfunction "PMODE0_45") (pintype "passive"))
    )
    (net (code "66") (name "Net-(U1-PMODE1)") (class "Default")
      (node (ref "R2") (pin "2") (pinfunction "2_2") (pintype "passive"))
      (node (ref "U1") (pin "44") (pinfunction "PMODE1_44") (pintype "passive"))
    )
    (net (code "67") (name "Net-(U1-PMODE2)") (class "Default")
      (node (ref "R2") (pin "3") (pinfunction "3_3") (pintype "passive"))
      (node (ref "U1") (pin "43") (pinfunction "PMODE2_43") (pintype "passive"))
    )
    (net (code "68") (name "Net-(U1-RXN)") (class "Default")
      (node (ref "C17") (pin "1") (pinfunction "1_1") (pintype "passive"))
      (node (ref "R15") (pin "1") (pinfunction "1_1") (pintype "passive"))
      (node (ref "U1") (pin "5") (pinfunction "RXN_5") (pintype "passive"))
    )
    (net (code "69") (name "Net-(U1-RXP)") (class "Default")
      (node (ref "C19") (pin "1") (pinfunction "1_1") (pintype "passive"))
      (node (ref "R16") (pin "1") (pinfunction "1_1") (pintype "passive"))
      (node (ref "U1") (pin "6") (pinfunction "RXP_6") (pintype "passive"))
    )
    (net (code "70") (name "Net-(U1-TOCAP)") (class "Default")
      (node (ref "C113") (pin "1") (pinfunction "1_1") (pintype "passive"))
      (node (ref "U1") (pin "20") (pinfunction "TOCAP_20") (pintype "passive"))
    )
    (net (code "71") (name "Net-(U1-TXN)") (class "Default")
      (node (ref "R17") (pin "1") (pinfunction "1_1") (pintype "passive"))
      (node (ref "T2") (pin "3") (pinfunction "3_3") (pintype "passive"))
      (node (ref "U1") (pin "1") (pinfunction "TXN_1") (pintype "passive"))
    )
    (net (code "72") (name "Net-(U1-TXP)") (class "Default")
      (node (ref "R19") (pin "1") (pinfunction "1_1") (pintype "passive"))
      (node (ref "T2") (pin "1") (pinfunction "1_1") (pintype "passive"))
      (node (ref "U1") (pin "2") (pinfunction "TXP_2") (pintype "passive"))
    )
    (net (code "73") (name "Net-(U1-XI{slash}CLKIN)") (class "Default")
      (node (ref "C9") (pin "1") (pinfunction "1_1") (pintype "passive"))
      (node (ref "Q3") (pin "2") (pinfunction "2_2") (pintype "passive"))
      (node (ref "R10") (pin "2") (pinfunction "2_2") (pintype "passive"))
      (node (ref "U1") (pin "30") (pinfunction "XI/CLKIN_30") (pintype "passive"))
    )
    (net (code "74") (name "Net-(U1-XO)") (class "Default")
      (node (ref "C8") (pin "2") (pinfunction "2_2") (pintype "passive"))
      (node (ref "Q3") (pin "1") (pinfunction "1_1") (pintype "passive"))
      (node (ref "R10") (pin "1") (pinfunction "1_1") (pintype "passive"))
      (node (ref "U1") (pin "31") (pinfunction "XO_31") (pintype "passive"))
    )
    (net (code "75") (name "Net-(U2-(HWB)PE2)") (class "Default")
      (node (ref "R21") (pin "1") (pinfunction "1_1") (pintype "passive"))
      (node (ref "U2") (pin "33") (pinfunction "(HWB)PE2_33") (pintype "bidirectional"))
    )
    (net (code "76") (name "Net-(U2-AREF)") (class "Default")
      (node (ref "C14") (pin "1") (pinfunction "1_1") (pintype "passive"))
      (node (ref "U2") (pin "42") (pinfunction "AREF_42") (pintype "bidirectional"))
    )
    (net (code "77") (name "Net-(U2-UCAP)") (class "Default")
      (node (ref "C13") (pin "2") (pinfunction "2_2") (pintype "passive"))
      (node (ref "U2") (pin "6") (pinfunction "UCAP_6") (pintype "bidirectional"))
    )
    (net (code "78") (name "Net-(U2-XTAL1)") (class "Default")
      (node (ref "C11") (pin "2") (pinfunction "2_2") (pintype "passive"))
      (node (ref "Q4") (pin "1") (pinfunction "1_1") (pintype "passive"))
      (node (ref "U2") (pin "17") (pinfunction "XTAL1_17") (pintype "bidirectional"))
    )
    (net (code "79") (name "Net-(U2-XTAL2)") (class "Default")
      (node (ref "C10") (pin "1") (pinfunction "1_1") (pintype "passive"))
      (node (ref "Q4") (pin "2") (pinfunction "2_2") (pintype "passive"))
      (node (ref "U2") (pin "16") (pinfunction "XTAL2_16") (pintype "bidirectional"))
    )
    (net (code "80") (name "Net-(X3A-KL)") (class "Default")
      (node (ref "R13") (pin "1") (pinfunction "1_1") (pintype "passive"))
      (node (ref "R37") (pin "1") (pinfunction "1_1") (pintype "passive"))
      (node (ref "X3") (pin "1") (pinfunction "KL_1") (pintype "passive"))
    )
    (net (code "81") (name "Net-(X5A-KL)") (class "Default")
      (node (ref "R27") (pin "1") (pinfunction "1_1") (pintype "passive"))
      (node (ref "X5") (pin "1") (pinfunction "KL_1") (pintype "passive"))
    )
    (net (code "82") (name "Net-(X5B-KL)") (class "Default")
      (node (ref "R26") (pin "1") (pinfunction "1_1") (pintype "passive"))
      (node (ref "X5") (pin "2") (pinfunction "KL_2") (pintype "passive"))
    )
    (net (code "83") (name "Net-(X8A-KL)") (class "Default")
      (node (ref "JMP2") (pin "2") (pinfunction "2_2") (pintype "passive"))
      (node (ref "X8") (pin "1") (pinfunction "KL_1") (pintype "passive"))
    )
    (net (code "84") (name "Net-(X8B-KL)") (class "Default")
      (node (ref "JMP1") (pin "2") (pinfunction "2_2") (pintype "passive"))
      (node (ref "X8") (pin "2") (pinfunction "KL_2") (pintype "passive"))
    )
    (net (code "85") (name "Net-(X9A-KL)") (class "Default")
      (node (ref "R25") (pin "1") (pinfunction "1_1") (pintype "passive"))
      (node (ref "X9") (pin "1") (pinfunction "KL_1") (pintype "passive"))
    )
    (net (code "86") (name "Net-(X9B-KL)") (class "Default")
      (node (ref "R14") (pin "1") (pinfunction "1_1") (pintype "passive"))
      (node (ref "X9") (pin "2") (pinfunction "KL_2") (pintype "passive"))
    )
    (net (code "87") (name "Net-(X10A-KL)") (class "Default")
      (node (ref "R30") (pin "1") (pinfunction "1_1") (pintype "passive"))
      (node (ref "SV4") (pin "8") (pinfunction "8_8") (pintype "passive"))
      (node (ref "T2") (pin "9") (pinfunction "9_9") (pintype "passive"))
      (node (ref "X10") (pin "1") (pinfunction "KL_1") (pintype "passive"))
    )
    (net (code "88") (name "Net-(X10B-KL)") (class "Default")
      (node (ref "R29") (pin "1") (pinfunction "1_1") (pintype "passive"))
      (node (ref "SV4") (pin "10") (pinfunction "10_10") (pintype "passive"))
      (node (ref "T2") (pin "11") (pinfunction "11_11") (pintype "passive"))
      (node (ref "X10") (pin "2") (pinfunction "KL_2") (pintype "passive"))
    )
    (net (code "89") (name "Net-(X10C-KL)") (class "Default")
      (node (ref "C15") (pin "2") (pinfunction "2_2") (pintype "passive"))
      (node (ref "C16") (pin "1") (pinfunction "1_1") (pintype "passive"))
      (node (ref "X10") (pin "3") (pinfunction "KL_3") (pintype "passive"))
    )
    (net (code "90") (name "Net-(X10D-KL)") (class "Default")
      (node (ref "SV4") (pin "9") (pinfunction "9_9") (pintype "passive"))
      (node (ref "T2") (pin "14") (pinfunction "14_14") (pintype "passive"))
      (node (ref "X10") (pin "4") (pinfunction "KL_4") (pintype "passive"))
    )
    (net (code "91") (name "Net-(X10E-KL)") (class "Default")
      (node (ref "SV4") (pin "7") (pinfunction "7_7") (pintype "passive"))
      (node (ref "T2") (pin "16") (pinfunction "16_16") (pintype "passive"))
      (node (ref "X10") (pin "5") (pinfunction "KL_5") (pintype "passive"))
    )
    (net (code "92") (name "Net-(X11A-KL)") (class "Default")
      (node (ref "R35") (pin "1") (pinfunction "1_1") (pintype "passive"))
      (node (ref "R36") (pin "2") (pinfunction "2_2") (pintype "passive"))
      (node (ref "SV5") (pin "3") (pinfunction "3_3") (pintype "passive"))
      (node (ref "X11") (pin "1") (pinfunction "KL_1") (pintype "passive"))
    )
    (net (code "93") (name "VCC") (class "Default")
      (node (ref "Q1") (pin "3") (pinfunction "D_3") (pintype "passive"))
      (node (ref "SV4") (pin "5") (pinfunction "5_5") (pintype "passive"))
      (node (ref "X1") (pin "1") (pinfunction "KL_1") (pintype "passive"))
    )
    (net (code "94") (name "unconnected-(IC6A-R2OUT-Pad9)") (class "Default")
      (node (ref "IC6") (pin "9") (pinfunction "R2OUT_9") (pintype "output"))
    )
    (net (code "95") (name "unconnected-(IC6A-T2OUT-Pad7)") (class "Default")
      (node (ref "IC6") (pin "7") (pinfunction "T2OUT_7") (pintype "output"))
    )
    (net (code "96") (name "unconnected-(U1-DNC-Pad7)") (class "Default")
      (node (ref "U1") (pin "7") (pinfunction "DNC_7") (pintype "passive"))
    )
    (net (code "97") (name "unconnected-(U1-DUPLED-Pad26)") (class "Default")
      (node (ref "U1") (pin "26") (pinfunction "DUPLED_26") (pintype "passive"))
    )
    (net (code "98") (name "unconnected-(U1-INT_N-Pad36)") (class "Default")
      (node (ref "U1") (pin "36") (pinfunction "INT_N_36") (pintype "passive"))
    )
    (net (code "99") (name "unconnected-(U1-NC-Pad12)") (class "Default")
      (node (ref "U1") (pin "12") (pinfunction "NC_12") (pintype "passive"))
    )
    (net (code "100") (name "unconnected-(U1-NC-Pad13)") (class "Default")
      (node (ref "U1") (pin "13") (pinfunction "NC_13") (pintype "passive"))
    )
    (net (code "101") (name "unconnected-(U1-NC-Pad46)") (class "Default")
      (node (ref "U1") (pin "46") (pinfunction "NC_46") (pintype "passive"))
    )
    (net (code "102") (name "unconnected-(U1-NC-Pad47)") (class "Default")
      (node (ref "U1") (pin "47") (pinfunction "NC_47") (pintype "passive"))
    )
    (net (code "103") (name "unconnected-(U1-SPDLED-Pad24)") (class "Default")
      (node (ref "U1") (pin "24") (pinfunction "SPDLED_24") (pintype "passive"))
    )
    (net (code "104") (name "unconnected-(U1-VBG-Pad18)") (class "Default")
      (node (ref "U1") (pin "18") (pinfunction "VBG_18") (pintype "passive"))
    )
    (net (code "105") (name "unconnected-(U2-(ADC4{slash}TCK)PF4-Pad39)") (class "Default")
      (node (ref "U2") (pin "39") (pinfunction "(ADC4/TCK)PF4_39") (pintype "bidirectional"))
    )
    (net (code "106") (name "unconnected-(U2-(ADC5{slash}TMS)PF5-Pad38)") (class "Default")
      (node (ref "U2") (pin "38") (pinfunction "(ADC5/TMS)PF5_38") (pintype "bidirectional"))
    )
    (net (code "107") (name "unconnected-(U2-(ADC6{slash}TDO)PF6-Pad37)") (class "Default")
      (node (ref "U2") (pin "37") (pinfunction "(ADC6/TDO)PF6_37") (pintype "bidirectional"))
    )
    (net (code "108") (name "unconnected-(U2-(ADC7{slash}TDI)PF7-Pad36)") (class "Default")
      (node (ref "U2") (pin "36") (pinfunction "(ADC7/TDI)PF7_36") (pintype "bidirectional"))
    )
    (net (code "109") (name "unconnected-(U2-(ICP1{slash}ADC8)PD4-Pad25)") (class "Default")
      (node (ref "U2") (pin "25") (pinfunction "(ICP1/ADC8)PD4_25") (pintype "bidirectional"))
    )
    (net (code "110") (name "unconnected-(U2-(PCINT4{slash}ADC11)PB4-Pad28)") (class "Default")
      (node (ref "U2") (pin "28") (pinfunction "(PCINT4/ADC11)PB4_28") (pintype "bidirectional"))
    )
    (net (code "111") (name "unconnected-(U2-(PCINT7{slash}OC0A{slash}OC1C{slash}RTS)PB7-Pad12)") (class "Default")
      (node (ref "U2") (pin "12") (pinfunction "(PCINT7/OC0A/OC1C/RTS)PB7_12") (pintype "bidirectional"))
    )
    (net (code "112") (name "unconnected-(U2-(SS{slash}PCINT0)PB0-Pad8)") (class "Default")
      (node (ref "U2") (pin "8") (pinfunction "(SS/PCINT0)PB0_8") (pintype "bidirectional"))
    )
    (net (code "113") (name "unconnected-(U2-(XCK1{slash}CTS)PD5-Pad22)") (class "Default")
      (node (ref "U2") (pin "22") (pinfunction "(XCK1/CTS)PD5_22") (pintype "bidirectional"))
    )
    (net (code "114") (name "unconnected-(X2-Pad4)") (class "Default")
      (node (ref "X2") (pin "4") (pinfunction "4_4") (pintype "passive"))
    )
  )
)
